# do_an1_easyeda.net
KiCad netlist of a schematic drawn in EasyEDA Pro
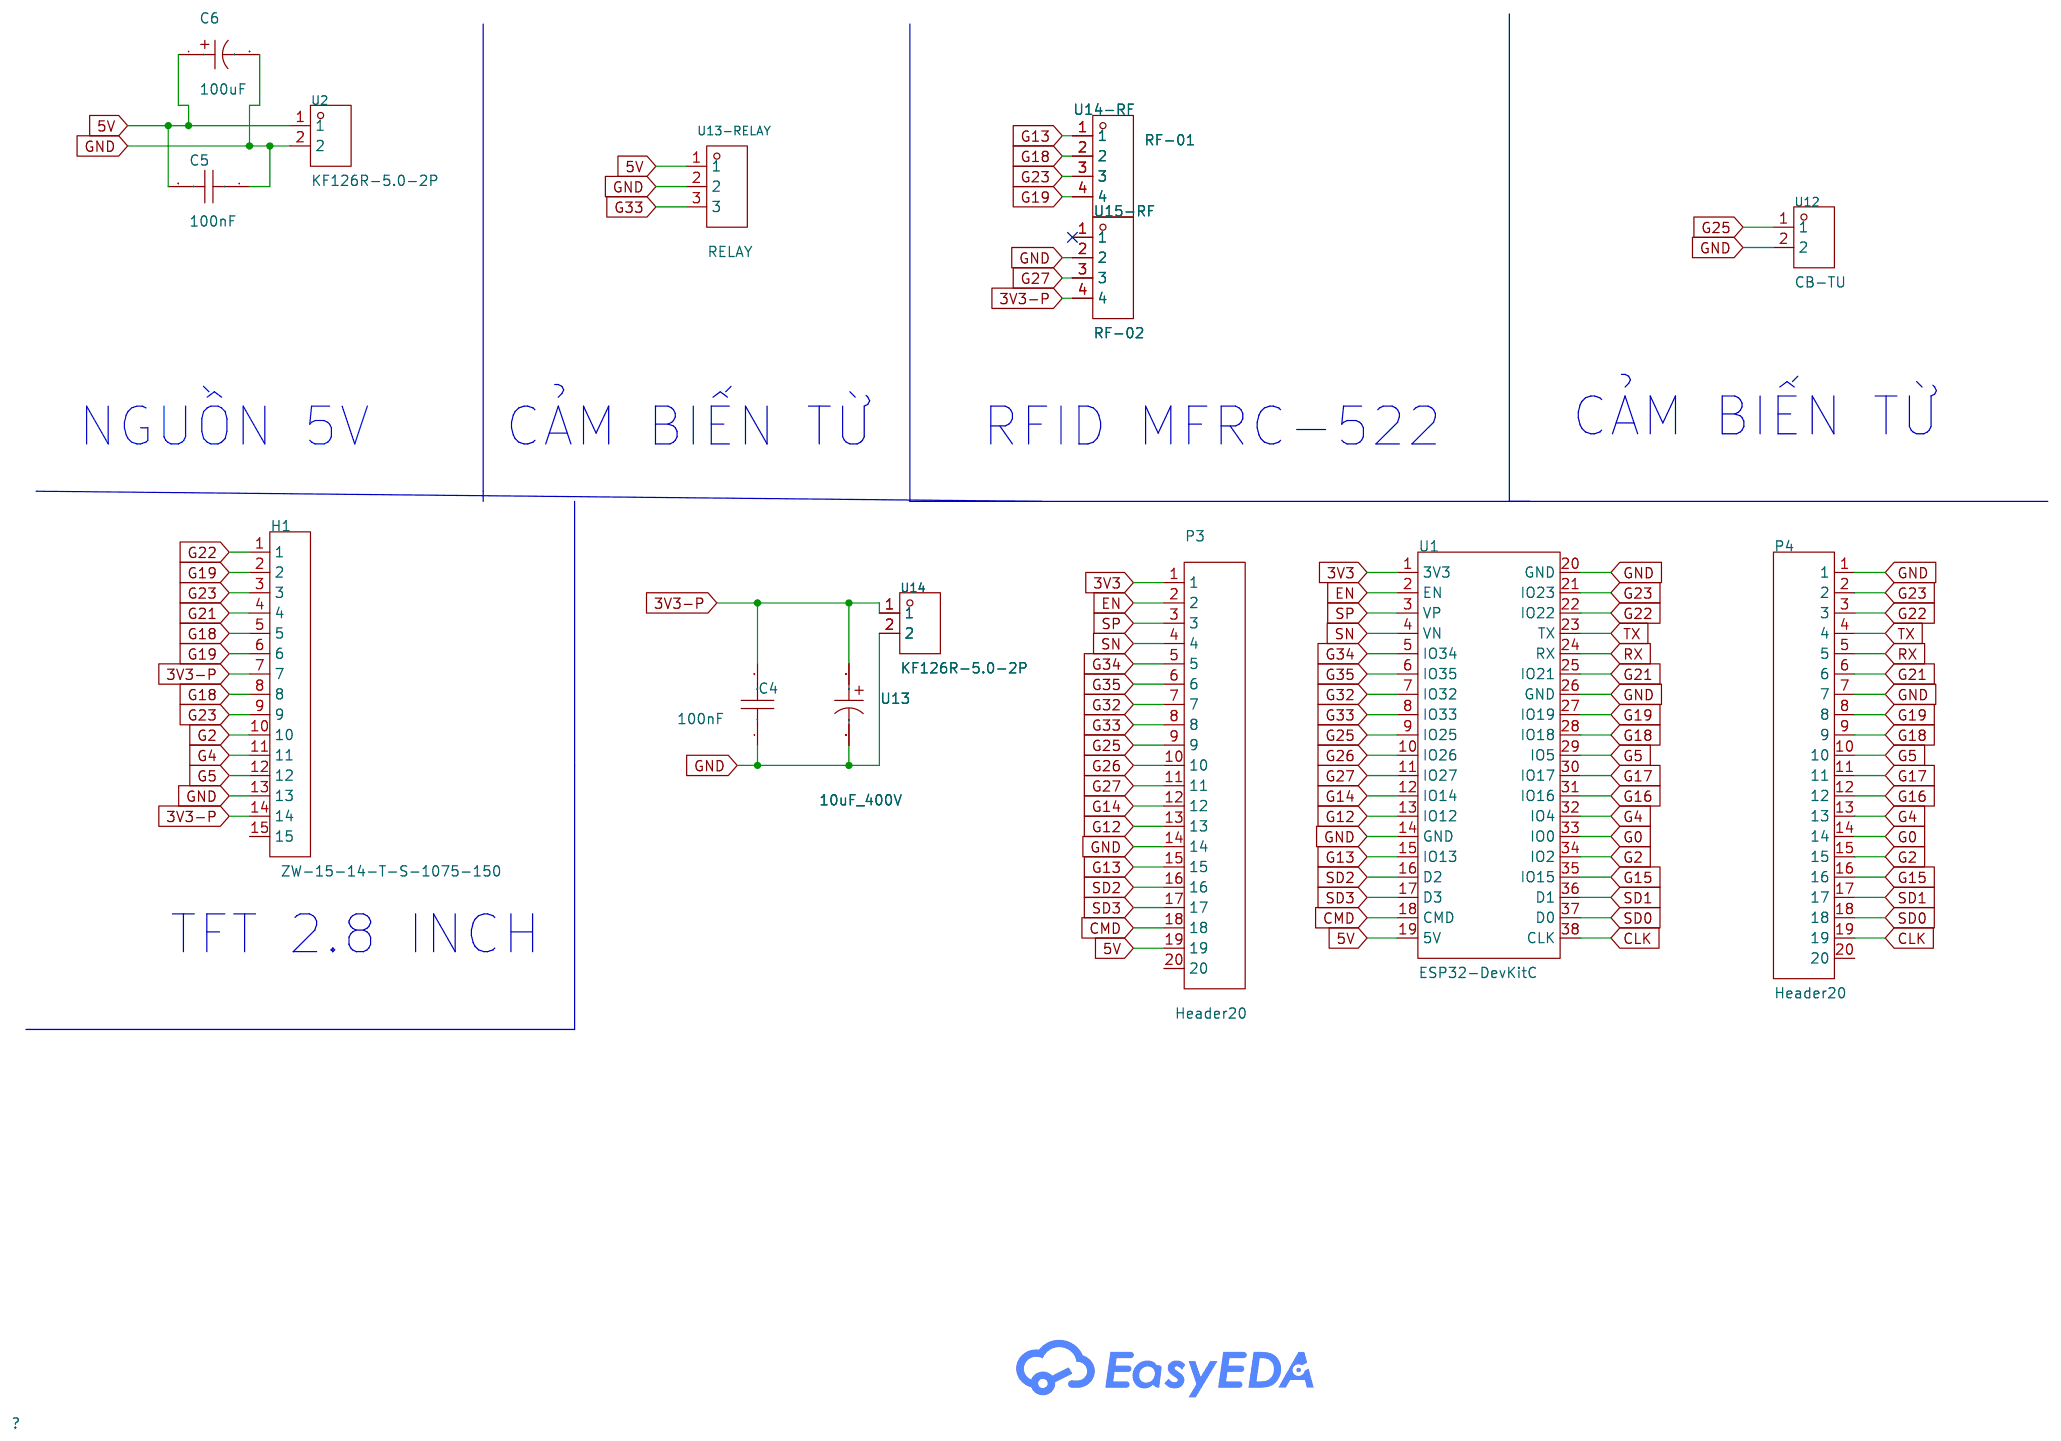
[diagram p0: schematic sheet]

(export (version "E")
  (design (tool "Eeschema 10.0.6"))
  (components
    (comp (ref "C4")
      (value "100nF")
      (footprint "easyedapro:CAP-TH_L5.0-W2.5-P5.00-D1.0")
      (fields
        (field (name "Manufacturer Part") "CC1H104MC1FD3F6C10MF")
        (field (name "Manufacturer") "Dersonic(德尔创)")
      )
      (libsource (lib "easyedapro") (part "CC1H104MC1FD3F6C10MF"))
    )
    (comp (ref "C5")
      (value "100nF")
      (footprint "easyedapro:CAP-TH_L5.0-W2.5-P5.00-D1.0")
      (fields
        (field (name "Manufacturer Part") "CC1H104MC1FD3F6C10MF")
        (field (name "Manufacturer") "Dersonic(德尔创)")
      )
      (libsource (lib "easyedapro") (part "CC1H104MC1FD3F6C10MF"))
    )
    (comp (ref "C6")
      (value "100uF")
      (footprint "easyedapro:CAP-TH_BD6.3-P2.50-D0.6-FD-H12.0-1")
      (fields (field (name "Manufacturer Part") "CD288H1HM101E120T") (field (name "Manufacturer") "CH(创慧电子)"))
      (libsource (lib "easyedapro") (part "CD288H1HM101E120T"))
    )
    (comp (ref "H1")
      (value "ZW-15-14-T-S-1075-150")
      (footprint "easyedapro:HDR-TH_DW-15-09-S-S-415")
      (fields (field (name "Manufacturer") "SAMTEC"))
      (libsource (lib "easyedapro") (part "ZW-15-14-T-S-1075-150"))
    )
    (comp (ref "P3")
      (value "Header20")
      (footprint "easyedapro:HDR-TH_20P-P2.54-V-M-1")
      (fields (field (name "Manufacturer") "Ckmtw(灿科盟)"))
      (libsource (lib "easyedapro") (part "210S-1*20P L=11.6MMGold-plated black"))
    )
    (comp (ref "P4")
      (value "Header20")
      (footprint "easyedapro:HDR-TH_20P-P2.54-V-M-1")
      (fields (field (name "Manufacturer") "Ckmtw(灿科盟)"))
      (libsource (lib "easyedapro") (part "210S-1*20P L=11.6MMGold-plated black"))
    )
    (comp (ref "U1")
      (value "ESP32-DevKitC")
      (footprint "easyedapro:BULETM-SMD_ESP32-DEVKITC")
      (fields (field (name "Manufacturer") "ESPRESSIF(乐鑫)"))
      (libsource (lib "easyedapro") (part "ESP32-DEVKITC"))
    )
    (comp (ref "U2")
      (value "KF126R-5.0-2P")
      (footprint "easyedapro:CONN-TH_P5.00_KF126R-5.0-2P")
      (fields (field (name "Manufacturer") "KEFA(科发)"))
      (libsource (lib "easyedapro") (part "KF126R-5.0-2P"))
    )
    (comp (ref "U12")
      (value "CB-TU")
      (footprint "easyedapro:CONN-TH_P5.00_KF126R-5.0-2P")
      (fields (field (name "Manufacturer") "KEFA(科发)"))
      (libsource (lib "easyedapro") (part "KF126R-5.0-2P"))
    )
    (comp (ref "U13")
      (value "10uF_400V")
      (footprint "easyedapro:CAP-TH_BD10.0-P5.00-D0.6-FD")
      (libsource (lib "easyedapro") (part "10UF_400V"))
    )
    (comp (ref "U13-RELAY")
      (value "RELAY")
      (footprint "easyedapro:CONN-TH_3P-P5.00_KF126R-5.0-3P")
      (fields (field (name "Manufacturer") "KEFA(科发)"))
      (libsource (lib "easyedapro") (part "KF126R-5.0-3P"))
    )
    (comp (ref "U14")
      (value "KF126R-5.0-2P")
      (footprint "easyedapro:CONN-TH_P5.00_KF126R-5.0-2P")
      (fields (field (name "Manufacturer") "KEFA(科发)"))
      (libsource (lib "easyedapro") (part "KF126R-5.0-2P"))
    )
    (comp (ref "U14-RF")
      (value "RF-01")
      (footprint "easyedapro:HDR-TH_4P-P2.54-V-M-4")
      (libsource (lib "easyedapro") (part "PH254-104-21MM"))
    )
    (comp (ref "U15-RF")
      (value "RF-02")
      (footprint "easyedapro:HDR-TH_4P-P2.54-V-M-4")
      (libsource (lib "easyedapro") (part "PH254-104-21MM"))
    )
  )
  (nets
    (net (code "1") (name "3V3") (class "Default")
      (node (ref "P3") (pin "1") (pinfunction "1_1") (pintype "unspecified"))
      (node (ref "U1") (pin "1") (pinfunction "3V3_1") (pintype "unspecified"))
    )
    (net (code "2") (name "3V3-P") (class "Default")
      (node (ref "C4") (pin "2") (pinfunction "2_2") (pintype "unspecified"))
      (node (ref "H1") (pin "14") (pinfunction "14_14") (pintype "unspecified"))
      (node (ref "H1") (pin "7") (pinfunction "7_7") (pintype "unspecified"))
      (node (ref "U13") (pin "1") (pinfunction "1_1") (pintype "input"))
      (node (ref "U14") (pin "1") (pinfunction "1_1") (pintype "input"))
      (node (ref "U15-RF") (pin "4") (pinfunction "4_4") (pintype "input"))
    )
    (net (code "3") (name "5V") (class "Default")
      (node (ref "C5") (pin "2") (pinfunction "2_2") (pintype "unspecified"))
      (node (ref "C6") (pin "1") (pinfunction "1_1") (pintype "input"))
      (node (ref "P3") (pin "19") (pinfunction "19_19") (pintype "unspecified"))
      (node (ref "U1") (pin "19") (pinfunction "5V_19") (pintype "unspecified"))
      (node (ref "U13-RELAY") (pin "1") (pinfunction "1_1") (pintype "input"))
      (node (ref "U2") (pin "1") (pinfunction "1_1") (pintype "input"))
    )
    (net (code "4") (name "CLK") (class "Default")
      (node (ref "P4") (pin "19") (pinfunction "19_19") (pintype "unspecified"))
      (node (ref "U1") (pin "38") (pinfunction "CLK_38") (pintype "unspecified"))
    )
    (net (code "5") (name "CMD") (class "Default")
      (node (ref "P3") (pin "18") (pinfunction "18_18") (pintype "unspecified"))
      (node (ref "U1") (pin "18") (pinfunction "CMD_18") (pintype "unspecified"))
    )
    (net (code "6") (name "EN") (class "Default")
      (node (ref "P3") (pin "2") (pinfunction "2_2") (pintype "unspecified"))
      (node (ref "U1") (pin "2") (pinfunction "EN_2") (pintype "unspecified"))
    )
    (net (code "7") (name "G0") (class "Default")
      (node (ref "P4") (pin "14") (pinfunction "14_14") (pintype "unspecified"))
      (node (ref "U1") (pin "33") (pinfunction "IO0_33") (pintype "unspecified"))
    )
    (net (code "8") (name "G2") (class "Default")
      (node (ref "H1") (pin "10") (pinfunction "10_10") (pintype "unspecified"))
      (node (ref "P4") (pin "15") (pinfunction "15_15") (pintype "unspecified"))
      (node (ref "U1") (pin "34") (pinfunction "IO2_34") (pintype "unspecified"))
    )
    (net (code "9") (name "G4") (class "Default")
      (node (ref "H1") (pin "11") (pinfunction "11_11") (pintype "unspecified"))
      (node (ref "P4") (pin "13") (pinfunction "13_13") (pintype "unspecified"))
      (node (ref "U1") (pin "32") (pinfunction "IO4_32") (pintype "unspecified"))
    )
    (net (code "10") (name "G5") (class "Default")
      (node (ref "H1") (pin "12") (pinfunction "12_12") (pintype "unspecified"))
      (node (ref "P4") (pin "10") (pinfunction "10_10") (pintype "unspecified"))
      (node (ref "U1") (pin "29") (pinfunction "IO5_29") (pintype "unspecified"))
    )
    (net (code "11") (name "G12") (class "Default")
      (node (ref "P3") (pin "13") (pinfunction "13_13") (pintype "unspecified"))
      (node (ref "U1") (pin "13") (pinfunction "IO12_13") (pintype "unspecified"))
    )
    (net (code "12") (name "G13") (class "Default")
      (node (ref "P3") (pin "15") (pinfunction "15_15") (pintype "unspecified"))
      (node (ref "U1") (pin "15") (pinfunction "IO13_15") (pintype "unspecified"))
      (node (ref "U14-RF") (pin "1") (pinfunction "1_1") (pintype "input"))
    )
    (net (code "13") (name "G14") (class "Default")
      (node (ref "P3") (pin "12") (pinfunction "12_12") (pintype "unspecified"))
      (node (ref "U1") (pin "12") (pinfunction "IO14_12") (pintype "unspecified"))
    )
    (net (code "14") (name "G15") (class "Default")
      (node (ref "P4") (pin "16") (pinfunction "16_16") (pintype "unspecified"))
      (node (ref "U1") (pin "35") (pinfunction "IO15_35") (pintype "unspecified"))
    )
    (net (code "15") (name "G16") (class "Default")
      (node (ref "P4") (pin "12") (pinfunction "12_12") (pintype "unspecified"))
      (node (ref "U1") (pin "31") (pinfunction "IO16_31") (pintype "unspecified"))
    )
    (net (code "16") (name "G17") (class "Default")
      (node (ref "P4") (pin "11") (pinfunction "11_11") (pintype "unspecified"))
      (node (ref "U1") (pin "30") (pinfunction "IO17_30") (pintype "unspecified"))
    )
    (net (code "17") (name "G18") (class "Default")
      (node (ref "H1") (pin "5") (pinfunction "5_5") (pintype "unspecified"))
      (node (ref "H1") (pin "8") (pinfunction "8_8") (pintype "unspecified"))
      (node (ref "P4") (pin "9") (pinfunction "9_9") (pintype "unspecified"))
      (node (ref "U1") (pin "28") (pinfunction "IO18_28") (pintype "unspecified"))
      (node (ref "U14-RF") (pin "2") (pinfunction "2_2") (pintype "input"))
    )
    (net (code "18") (name "G19") (class "Default")
      (node (ref "H1") (pin "2") (pinfunction "2_2") (pintype "unspecified"))
      (node (ref "H1") (pin "6") (pinfunction "6_6") (pintype "unspecified"))
      (node (ref "P4") (pin "8") (pinfunction "8_8") (pintype "unspecified"))
      (node (ref "U1") (pin "27") (pinfunction "IO19_27") (pintype "unspecified"))
      (node (ref "U14-RF") (pin "4") (pinfunction "4_4") (pintype "input"))
    )
    (net (code "19") (name "G21") (class "Default")
      (node (ref "H1") (pin "4") (pinfunction "4_4") (pintype "unspecified"))
      (node (ref "P4") (pin "6") (pinfunction "6_6") (pintype "unspecified"))
      (node (ref "U1") (pin "25") (pinfunction "IO21_25") (pintype "unspecified"))
    )
    (net (code "20") (name "G22") (class "Default")
      (node (ref "H1") (pin "1") (pinfunction "1_1") (pintype "unspecified"))
      (node (ref "P4") (pin "3") (pinfunction "3_3") (pintype "unspecified"))
      (node (ref "U1") (pin "22") (pinfunction "IO22_22") (pintype "unspecified"))
    )
    (net (code "21") (name "G23") (class "Default")
      (node (ref "H1") (pin "3") (pinfunction "3_3") (pintype "unspecified"))
      (node (ref "H1") (pin "9") (pinfunction "9_9") (pintype "unspecified"))
      (node (ref "P4") (pin "2") (pinfunction "2_2") (pintype "unspecified"))
      (node (ref "U1") (pin "21") (pinfunction "IO23_21") (pintype "unspecified"))
      (node (ref "U14-RF") (pin "3") (pinfunction "3_3") (pintype "input"))
    )
    (net (code "22") (name "G25") (class "Default")
      (node (ref "P3") (pin "9") (pinfunction "9_9") (pintype "unspecified"))
      (node (ref "U1") (pin "9") (pinfunction "IO25_9") (pintype "unspecified"))
      (node (ref "U12") (pin "1") (pinfunction "1_1") (pintype "input"))
    )
    (net (code "23") (name "G26") (class "Default")
      (node (ref "P3") (pin "10") (pinfunction "10_10") (pintype "unspecified"))
      (node (ref "U1") (pin "10") (pinfunction "IO26_10") (pintype "unspecified"))
    )
    (net (code "24") (name "G27") (class "Default")
      (node (ref "P3") (pin "11") (pinfunction "11_11") (pintype "unspecified"))
      (node (ref "U1") (pin "11") (pinfunction "IO27_11") (pintype "unspecified"))
      (node (ref "U15-RF") (pin "3") (pinfunction "3_3") (pintype "input"))
    )
    (net (code "25") (name "G32") (class "Default")
      (node (ref "P3") (pin "7") (pinfunction "7_7") (pintype "unspecified"))
      (node (ref "U1") (pin "7") (pinfunction "IO32_7") (pintype "unspecified"))
    )
    (net (code "26") (name "G33") (class "Default")
      (node (ref "P3") (pin "8") (pinfunction "8_8") (pintype "unspecified"))
      (node (ref "U1") (pin "8") (pinfunction "IO33_8") (pintype "unspecified"))
      (node (ref "U13-RELAY") (pin "3") (pinfunction "3_3") (pintype "input"))
    )
    (net (code "27") (name "G34") (class "Default")
      (node (ref "P3") (pin "5") (pinfunction "5_5") (pintype "unspecified"))
      (node (ref "U1") (pin "5") (pinfunction "IO34_5") (pintype "unspecified"))
    )
    (net (code "28") (name "G35") (class "Default")
      (node (ref "P3") (pin "6") (pinfunction "6_6") (pintype "unspecified"))
      (node (ref "U1") (pin "6") (pinfunction "IO35_6") (pintype "unspecified"))
    )
    (net (code "29") (name "GND") (class "Default")
      (node (ref "C4") (pin "1") (pinfunction "1_1") (pintype "unspecified"))
      (node (ref "C5") (pin "1") (pinfunction "1_1") (pintype "unspecified"))
      (node (ref "C6") (pin "2") (pinfunction "2_2") (pintype "input"))
      (node (ref "H1") (pin "13") (pinfunction "13_13") (pintype "unspecified"))
      (node (ref "P3") (pin "14") (pinfunction "14_14") (pintype "unspecified"))
      (node (ref "P4") (pin "1") (pinfunction "1_1") (pintype "unspecified"))
      (node (ref "P4") (pin "7") (pinfunction "7_7") (pintype "unspecified"))
      (node (ref "U1") (pin "14") (pinfunction "GND_14") (pintype "unspecified"))
      (node (ref "U1") (pin "20") (pinfunction "GND_20") (pintype "unspecified"))
      (node (ref "U1") (pin "26") (pinfunction "GND_26") (pintype "unspecified"))
      (node (ref "U12") (pin "2") (pinfunction "2_2") (pintype "input"))
      (node (ref "U13") (pin "2") (pinfunction "2_2") (pintype "input"))
      (node (ref "U13-RELAY") (pin "2") (pinfunction "2_2") (pintype "input"))
      (node (ref "U14") (pin "2") (pinfunction "2_2") (pintype "input"))
      (node (ref "U15-RF") (pin "2") (pinfunction "2_2") (pintype "input"))
      (node (ref "U2") (pin "2") (pinfunction "2_2") (pintype "input"))
    )
    (net (code "30") (name "RX") (class "Default")
      (node (ref "P4") (pin "5") (pinfunction "5_5") (pintype "unspecified"))
      (node (ref "U1") (pin "24") (pinfunction "RX_24") (pintype "unspecified"))
    )
    (net (code "31") (name "SD0") (class "Default")
      (node (ref "P4") (pin "18") (pinfunction "18_18") (pintype "unspecified"))
      (node (ref "U1") (pin "37") (pinfunction "D0_37") (pintype "unspecified"))
    )
    (net (code "32") (name "SD1") (class "Default")
      (node (ref "P4") (pin "17") (pinfunction "17_17") (pintype "unspecified"))
      (node (ref "U1") (pin "36") (pinfunction "D1_36") (pintype "unspecified"))
    )
    (net (code "33") (name "SD2") (class "Default")
      (node (ref "P3") (pin "16") (pinfunction "16_16") (pintype "unspecified"))
      (node (ref "U1") (pin "16") (pinfunction "D2_16") (pintype "unspecified"))
    )
    (net (code "34") (name "SD3") (class "Default")
      (node (ref "P3") (pin "17") (pinfunction "17_17") (pintype "unspecified"))
      (node (ref "U1") (pin "17") (pinfunction "D3_17") (pintype "unspecified"))
    )
    (net (code "35") (name "SN") (class "Default")
      (node (ref "P3") (pin "4") (pinfunction "4_4") (pintype "unspecified"))
      (node (ref "U1") (pin "4") (pinfunction "VN_4") (pintype "unspecified"))
    )
    (net (code "36") (name "SP") (class "Default")
      (node (ref "P3") (pin "3") (pinfunction "3_3") (pintype "unspecified"))
      (node (ref "U1") (pin "3") (pinfunction "VP_3") (pintype "unspecified"))
    )
    (net (code "37") (name "TX") (class "Default")
      (node (ref "P4") (pin "4") (pinfunction "4_4") (pintype "unspecified"))
      (node (ref "U1") (pin "23") (pinfunction "TX_23") (pintype "unspecified"))
    )
    (net (code "38") (name "unconnected-(H1-Pad15)") (class "Default")
      (node (ref "H1") (pin "15") (pinfunction "15_15") (pintype "unspecified"))
    )
    (net (code "39") (name "unconnected-(P3-Pad20)") (class "Default")
      (node (ref "P3") (pin "20") (pinfunction "20_20") (pintype "unspecified"))
    )
    (net (code "40") (name "unconnected-(P4-Pad20)") (class "Default")
      (node (ref "P4") (pin "20") (pinfunction "20_20") (pintype "unspecified"))
    )
    (net (code "41") (name "unconnected-(U15-RF-Pad1)") (class "Default")
      (node (ref "U15-RF") (pin "1") (pinfunction "1_1") (pintype "input+no_connect"))
    )
  )
)
